# Nucleo.net
KiCad netlist of a schematic drawn in Altium Designer
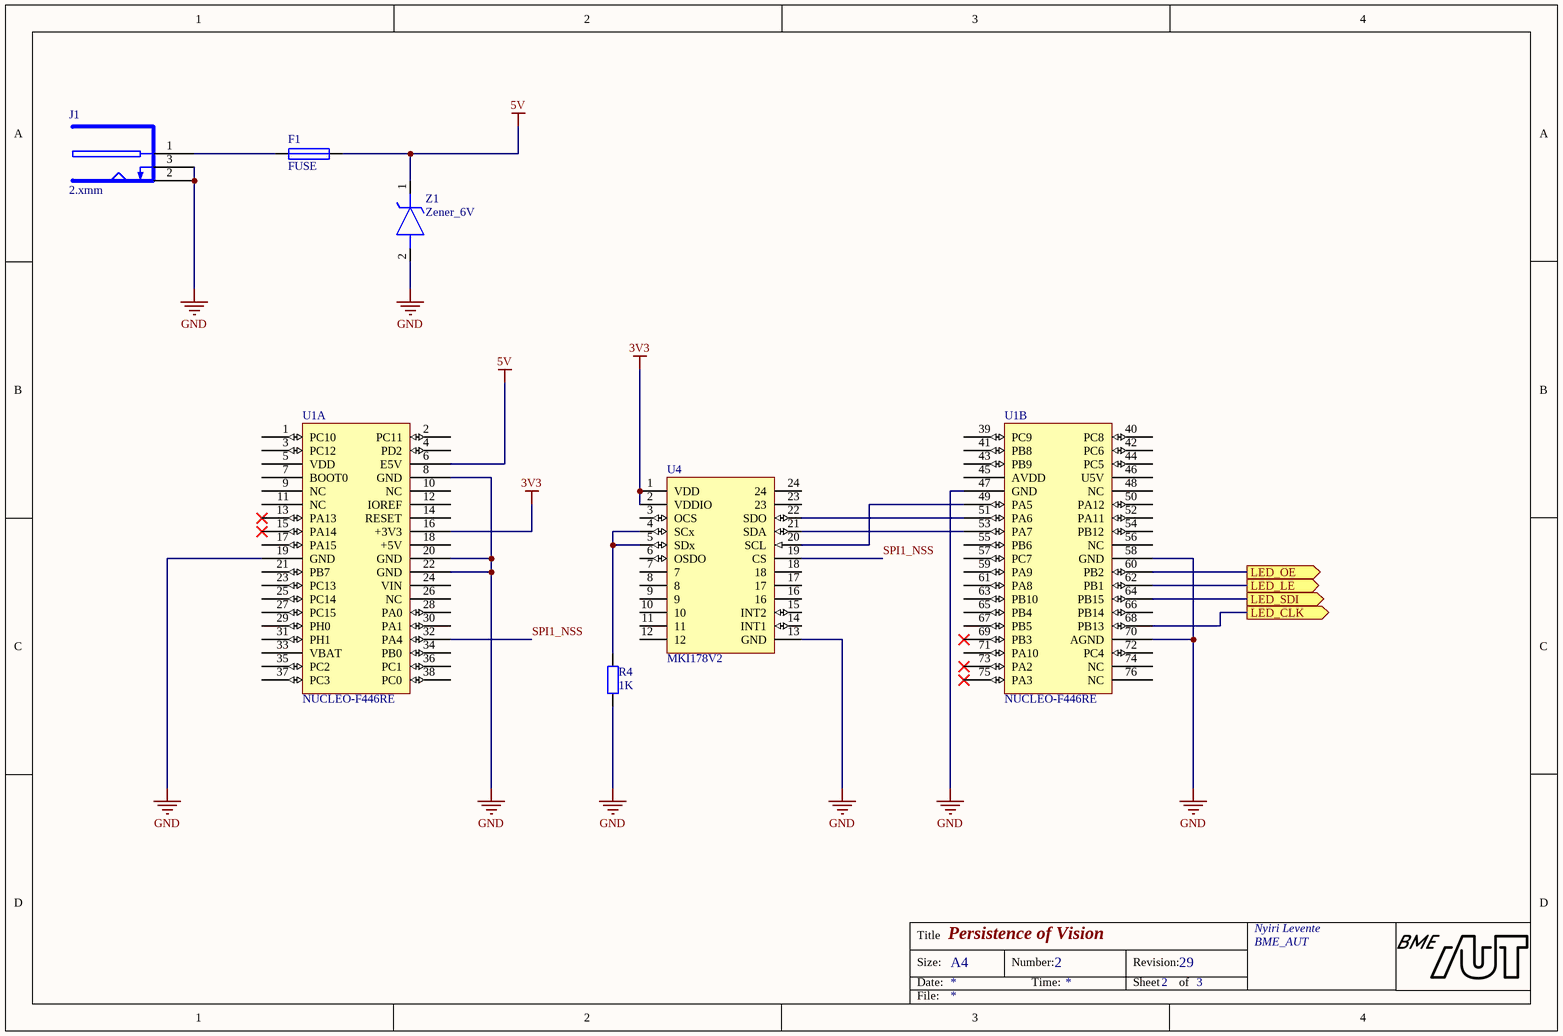
[diagram p0: Nucleo.SchDoc]

(export (version "E")
  (design (tool "Eeschema 10.0.6"))
  (components
    (comp (ref "F1")
      (value "FUSE")
      (footprint "1812L125/16DR2.0")
      (description "PTC Resettable Fuse, 16V, Surface Mount")
      (libsource (lib "hallglib") (part "1812L125/16DR"))
    )
    (comp (ref "J1")
      (value "2.xmm")
      (footprint "FP_DC_TAP_ANYA")
      (description "2.xmm DC HEBA25 TÁPFESZÜLTSÉG ALJZAT ZÁRT, NYÁKBA 90°")
      (libsource (lib "hallglib") (part "DC_TAP_ANYA"))
    )
    (comp (ref "R4")
      (value "1K")
      (footprint "FP_0805_RES")
      (description "Resistor")
      (libsource (lib "hallglib") (part "RES"))
    )
    (comp (ref "U1")
      (value "NUCLEO-F446RE")
      (footprint "FP_NUCLEO-64_2x20")
      (libsource (lib "hallglib") (part "NUCLEO-F446RE"))
    )
    (comp (ref "U4")
      (value "MKI178V2")
      (footprint "FP_DIL24")
      (description "LSM6DS3 inertial module adapter")
      (libsource (lib "hallglib") (part "MKI160V1"))
    )
    (comp (ref "Z1")
      (value "Zener_6V")
      (footprint "SOD2512X115N")
      (description "Zener Diode")
      (libsource (lib "hallglib") (part "BZT52C6V2S"))
    )
  )
  (nets
    (net (code "1") (name "/LED_CLK") (class "Default")
      (node (ref "U1") (pin "68") (pinfunction "PB13_68") (pintype "bidirectional"))
    )
    (net (code "2") (name "/LED_LE") (class "Default")
      (node (ref "U1") (pin "62") (pinfunction "PB1_62") (pintype "bidirectional"))
    )
    (net (code "3") (name "/LED_OE") (class "Default")
      (node (ref "U1") (pin "60") (pinfunction "PB2_60") (pintype "bidirectional"))
    )
    (net (code "4") (name "/LED_SDI") (class "Default")
      (node (ref "U1") (pin "64") (pinfunction "PB15_64") (pintype "bidirectional"))
    )
    (net (code "5") (name "/SPI1_NSS") (class "Default")
      (node (ref "U1") (pin "32") (pinfunction "PA4_32") (pintype "bidirectional"))
      (node (ref "U4") (pin "19") (pinfunction "CS_19") (pintype "passive"))
    )
    (net (code "6") (name "3V3") (class "Default")
      (node (ref "U1") (pin "16") (pinfunction "+3V3_16") (pintype "power_in"))
      (node (ref "U4") (pin "1") (pinfunction "VDD_1") (pintype "power_in"))
      (node (ref "U4") (pin "2") (pinfunction "VDDIO_2") (pintype "power_in"))
    )
    (net (code "7") (name "5V") (class "Default")
      (node (ref "F1") (pin "2") (pinfunction "2_2") (pintype "passive"))
      (node (ref "U1") (pin "6") (pinfunction "E5V_6") (pintype "power_in"))
      (node (ref "Z1") (pin "1") (pinfunction "K_1") (pintype "passive"))
    )
    (net (code "8") (name "GND") (class "Default")
      (node (ref "J1") (pin "2") (pinfunction "SLEEVE_2") (pintype "power_in"))
      (node (ref "J1") (pin "3") (pinfunction "BREAK_3") (pintype "power_in"))
      (node (ref "R4") (pin "1") (pinfunction "1_1") (pintype "passive"))
      (node (ref "U1") (pin "19") (pinfunction "GND_19") (pintype "passive"))
      (node (ref "U1") (pin "20") (pinfunction "GND_20") (pintype "passive"))
      (node (ref "U1") (pin "22") (pinfunction "GND_22") (pintype "passive"))
      (node (ref "U1") (pin "47") (pinfunction "GND_47") (pintype "passive"))
      (node (ref "U1") (pin "58") (pinfunction "GND_58") (pintype "passive"))
      (node (ref "U1") (pin "70") (pinfunction "AGND_70") (pintype "passive"))
      (node (ref "U1") (pin "8") (pinfunction "GND_8") (pintype "passive"))
      (node (ref "U4") (pin "13") (pinfunction "GND_13") (pintype "power_in"))
      (node (ref "Z1") (pin "2") (pinfunction "A_2") (pintype "passive"))
    )
    (net (code "9") (name "Net-(J1-PIN)") (class "Default")
      (node (ref "F1") (pin "1") (pinfunction "1_1") (pintype "passive"))
      (node (ref "J1") (pin "1") (pinfunction "PIN_1") (pintype "power_in"))
    )
    (net (code "10") (name "Net-(U1B-PA5)") (class "Default")
      (node (ref "U1") (pin "49") (pinfunction "PA5_49") (pintype "bidirectional"))
      (node (ref "U4") (pin "20") (pinfunction "SCL_20") (pintype "input"))
    )
    (net (code "11") (name "Net-(U1B-PA6)") (class "Default")
      (node (ref "U1") (pin "51") (pinfunction "PA6_51") (pintype "bidirectional"))
      (node (ref "U4") (pin "22") (pinfunction "SDO_22") (pintype "bidirectional"))
    )
    (net (code "12") (name "Net-(U1B-PA7)") (class "Default")
      (node (ref "U1") (pin "53") (pinfunction "PA7_53") (pintype "bidirectional"))
      (node (ref "U4") (pin "21") (pinfunction "SDA_21") (pintype "bidirectional"))
    )
    (net (code "13") (name "Net-(U4-SCx)") (class "Default")
      (node (ref "R4") (pin "2") (pinfunction "2_2") (pintype "passive"))
      (node (ref "U4") (pin "4") (pinfunction "SCx_4") (pintype "bidirectional"))
      (node (ref "U4") (pin "5") (pinfunction "SDx_5") (pintype "bidirectional"))
    )
    (net (code "14") (name "unconnected-(U1A-+5V-Pad18)") (class "Default")
      (node (ref "U1") (pin "18") (pinfunction "+5V_18") (pintype "power_in"))
    )
    (net (code "15") (name "unconnected-(U1A-BOOT0-Pad7)") (class "Default")
      (node (ref "U1") (pin "7") (pinfunction "BOOT0_7") (pintype "passive"))
    )
    (net (code "16") (name "unconnected-(U1A-IOREF-Pad12)") (class "Default")
      (node (ref "U1") (pin "12") (pinfunction "IOREF_12") (pintype "passive"))
    )
    (net (code "17") (name "unconnected-(U1A-NC-Pad9)") (class "Default")
      (node (ref "U1") (pin "9") (pinfunction "NC_9") (pintype "passive"))
    )
    (net (code "18") (name "unconnected-(U1A-NC-Pad10)") (class "Default")
      (node (ref "U1") (pin "10") (pinfunction "NC_10") (pintype "passive"))
    )
    (net (code "19") (name "unconnected-(U1A-NC-Pad11)") (class "Default")
      (node (ref "U1") (pin "11") (pinfunction "NC_11") (pintype "passive"))
    )
    (net (code "20") (name "unconnected-(U1A-NC-Pad26)") (class "Default")
      (node (ref "U1") (pin "26") (pinfunction "NC_26") (pintype "passive"))
    )
    (net (code "21") (name "unconnected-(U1A-PA0-Pad28)") (class "Default")
      (node (ref "U1") (pin "28") (pinfunction "PA0_28") (pintype "bidirectional"))
    )
    (net (code "22") (name "unconnected-(U1A-PA1-Pad30)") (class "Default")
      (node (ref "U1") (pin "30") (pinfunction "PA1_30") (pintype "bidirectional"))
    )
    (net (code "23") (name "unconnected-(U1A-PA13-Pad13)") (class "Default")
      (node (ref "U1") (pin "13") (pinfunction "PA13_13") (pintype "bidirectional+no_connect"))
    )
    (net (code "24") (name "unconnected-(U1A-PA14-Pad15)") (class "Default")
      (node (ref "U1") (pin "15") (pinfunction "PA14_15") (pintype "bidirectional+no_connect"))
    )
    (net (code "25") (name "unconnected-(U1A-PA15-Pad17)") (class "Default")
      (node (ref "U1") (pin "17") (pinfunction "PA15_17") (pintype "bidirectional"))
    )
    (net (code "26") (name "unconnected-(U1A-PB0-Pad34)") (class "Default")
      (node (ref "U1") (pin "34") (pinfunction "PB0_34") (pintype "bidirectional"))
    )
    (net (code "27") (name "unconnected-(U1A-PB7-Pad21)") (class "Default")
      (node (ref "U1") (pin "21") (pinfunction "PB7_21") (pintype "bidirectional"))
    )
    (net (code "28") (name "unconnected-(U1A-PC0-Pad38)") (class "Default")
      (node (ref "U1") (pin "38") (pinfunction "PC0_38") (pintype "bidirectional"))
    )
    (net (code "29") (name "unconnected-(U1A-PC1-Pad36)") (class "Default")
      (node (ref "U1") (pin "36") (pinfunction "PC1_36") (pintype "bidirectional"))
    )
    (net (code "30") (name "unconnected-(U1A-PC2-Pad35)") (class "Default")
      (node (ref "U1") (pin "35") (pinfunction "PC2_35") (pintype "bidirectional"))
    )
    (net (code "31") (name "unconnected-(U1A-PC3-Pad37)") (class "Default")
      (node (ref "U1") (pin "37") (pinfunction "PC3_37") (pintype "bidirectional"))
    )
    (net (code "32") (name "unconnected-(U1A-PC10-Pad1)") (class "Default")
      (node (ref "U1") (pin "1") (pinfunction "PC10_1") (pintype "bidirectional"))
    )
    (net (code "33") (name "unconnected-(U1A-PC11-Pad2)") (class "Default")
      (node (ref "U1") (pin "2") (pinfunction "PC11_2") (pintype "bidirectional"))
    )
    (net (code "34") (name "unconnected-(U1A-PC12-Pad3)") (class "Default")
      (node (ref "U1") (pin "3") (pinfunction "PC12_3") (pintype "bidirectional"))
    )
    (net (code "35") (name "unconnected-(U1A-PC13-Pad23)") (class "Default")
      (node (ref "U1") (pin "23") (pinfunction "PC13_23") (pintype "bidirectional"))
    )
    (net (code "36") (name "unconnected-(U1A-PC14-Pad25)") (class "Default")
      (node (ref "U1") (pin "25") (pinfunction "PC14_25") (pintype "bidirectional"))
    )
    (net (code "37") (name "unconnected-(U1A-PC15-Pad27)") (class "Default")
      (node (ref "U1") (pin "27") (pinfunction "PC15_27") (pintype "bidirectional"))
    )
    (net (code "38") (name "unconnected-(U1A-PD2-Pad4)") (class "Default")
      (node (ref "U1") (pin "4") (pinfunction "PD2_4") (pintype "bidirectional"))
    )
    (net (code "39") (name "unconnected-(U1A-PH0-Pad29)") (class "Default")
      (node (ref "U1") (pin "29") (pinfunction "PH0_29") (pintype "bidirectional"))
    )
    (net (code "40") (name "unconnected-(U1A-PH1-Pad31)") (class "Default")
      (node (ref "U1") (pin "31") (pinfunction "PH1_31") (pintype "bidirectional"))
    )
    (net (code "41") (name "unconnected-(U1A-RESET-Pad14)") (class "Default")
      (node (ref "U1") (pin "14") (pinfunction "RESET_14") (pintype "passive"))
    )
    (net (code "42") (name "unconnected-(U1A-VBAT-Pad33)") (class "Default")
      (node (ref "U1") (pin "33") (pinfunction "VBAT_33") (pintype "power_in"))
    )
    (net (code "43") (name "unconnected-(U1A-VDD-Pad5)") (class "Default")
      (node (ref "U1") (pin "5") (pinfunction "VDD_5") (pintype "power_in"))
    )
    (net (code "44") (name "unconnected-(U1A-VIN-Pad24)") (class "Default")
      (node (ref "U1") (pin "24") (pinfunction "VIN_24") (pintype "power_in"))
    )
    (net (code "45") (name "unconnected-(U1B-AVDD-Pad45)") (class "Default")
      (node (ref "U1") (pin "45") (pinfunction "AVDD_45") (pintype "power_in"))
    )
    (net (code "46") (name "unconnected-(U1B-NC-Pad48)") (class "Default")
      (node (ref "U1") (pin "48") (pinfunction "NC_48") (pintype "passive"))
    )
    (net (code "47") (name "unconnected-(U1B-NC-Pad56)") (class "Default")
      (node (ref "U1") (pin "56") (pinfunction "NC_56") (pintype "passive"))
    )
    (net (code "48") (name "unconnected-(U1B-NC-Pad74)") (class "Default")
      (node (ref "U1") (pin "74") (pinfunction "NC_74") (pintype "passive"))
    )
    (net (code "49") (name "unconnected-(U1B-NC-Pad76)") (class "Default")
      (node (ref "U1") (pin "76") (pinfunction "NC_76") (pintype "passive"))
    )
    (net (code "50") (name "unconnected-(U1B-PA2-Pad73)") (class "Default")
      (node (ref "U1") (pin "73") (pinfunction "PA2_73") (pintype "bidirectional+no_connect"))
    )
    (net (code "51") (name "unconnected-(U1B-PA3-Pad75)") (class "Default")
      (node (ref "U1") (pin "75") (pinfunction "PA3_75") (pintype "bidirectional+no_connect"))
    )
    (net (code "52") (name "unconnected-(U1B-PA8-Pad61)") (class "Default")
      (node (ref "U1") (pin "61") (pinfunction "PA8_61") (pintype "bidirectional"))
    )
    (net (code "53") (name "unconnected-(U1B-PA9-Pad59)") (class "Default")
      (node (ref "U1") (pin "59") (pinfunction "PA9_59") (pintype "bidirectional"))
    )
    (net (code "54") (name "unconnected-(U1B-PA10-Pad71)") (class "Default")
      (node (ref "U1") (pin "71") (pinfunction "PA10_71") (pintype "bidirectional"))
    )
    (net (code "55") (name "unconnected-(U1B-PA11-Pad52)") (class "Default")
      (node (ref "U1") (pin "52") (pinfunction "PA11_52") (pintype "bidirectional"))
    )
    (net (code "56") (name "unconnected-(U1B-PA12-Pad50)") (class "Default")
      (node (ref "U1") (pin "50") (pinfunction "PA12_50") (pintype "bidirectional"))
    )
    (net (code "57") (name "unconnected-(U1B-PB3-Pad69)") (class "Default")
      (node (ref "U1") (pin "69") (pinfunction "PB3_69") (pintype "bidirectional+no_connect"))
    )
    (net (code "58") (name "unconnected-(U1B-PB4-Pad65)") (class "Default")
      (node (ref "U1") (pin "65") (pinfunction "PB4_65") (pintype "bidirectional"))
    )
    (net (code "59") (name "unconnected-(U1B-PB5-Pad67)") (class "Default")
      (node (ref "U1") (pin "67") (pinfunction "PB5_67") (pintype "bidirectional"))
    )
    (net (code "60") (name "unconnected-(U1B-PB6-Pad55)") (class "Default")
      (node (ref "U1") (pin "55") (pinfunction "PB6_55") (pintype "bidirectional"))
    )
    (net (code "61") (name "unconnected-(U1B-PB8-Pad41)") (class "Default")
      (node (ref "U1") (pin "41") (pinfunction "PB8_41") (pintype "bidirectional"))
    )
    (net (code "62") (name "unconnected-(U1B-PB9-Pad43)") (class "Default")
      (node (ref "U1") (pin "43") (pinfunction "PB9_43") (pintype "bidirectional"))
    )
    (net (code "63") (name "unconnected-(U1B-PB10-Pad63)") (class "Default")
      (node (ref "U1") (pin "63") (pinfunction "PB10_63") (pintype "bidirectional"))
    )
    (net (code "64") (name "unconnected-(U1B-PB12-Pad54)") (class "Default")
      (node (ref "U1") (pin "54") (pinfunction "PB12_54") (pintype "bidirectional"))
    )
    (net (code "65") (name "unconnected-(U1B-PB14-Pad66)") (class "Default")
      (node (ref "U1") (pin "66") (pinfunction "PB14_66") (pintype "bidirectional"))
    )
    (net (code "66") (name "unconnected-(U1B-PC4-Pad72)") (class "Default")
      (node (ref "U1") (pin "72") (pinfunction "PC4_72") (pintype "bidirectional"))
    )
    (net (code "67") (name "unconnected-(U1B-PC5-Pad44)") (class "Default")
      (node (ref "U1") (pin "44") (pinfunction "PC5_44") (pintype "bidirectional"))
    )
    (net (code "68") (name "unconnected-(U1B-PC6-Pad42)") (class "Default")
      (node (ref "U1") (pin "42") (pinfunction "PC6_42") (pintype "bidirectional"))
    )
    (net (code "69") (name "unconnected-(U1B-PC7-Pad57)") (class "Default")
      (node (ref "U1") (pin "57") (pinfunction "PC7_57") (pintype "bidirectional"))
    )
    (net (code "70") (name "unconnected-(U1B-PC8-Pad40)") (class "Default")
      (node (ref "U1") (pin "40") (pinfunction "PC8_40") (pintype "bidirectional"))
    )
    (net (code "71") (name "unconnected-(U1B-PC9-Pad39)") (class "Default")
      (node (ref "U1") (pin "39") (pinfunction "PC9_39") (pintype "bidirectional"))
    )
    (net (code "72") (name "unconnected-(U1B-U5V-Pad46)") (class "Default")
      (node (ref "U1") (pin "46") (pinfunction "U5V_46") (pintype "power_in"))
    )
    (net (code "73") (name "unconnected-(U4-INT1-Pad14)") (class "Default")
      (node (ref "U4") (pin "14") (pinfunction "INT1_14") (pintype "bidirectional"))
    )
    (net (code "74") (name "unconnected-(U4-INT2-Pad15)") (class "Default")
      (node (ref "U4") (pin "15") (pinfunction "INT2_15") (pintype "bidirectional"))
    )
    (net (code "75") (name "unconnected-(U4-OCS-Pad3)") (class "Default")
      (node (ref "U4") (pin "3") (pinfunction "OCS_3") (pintype "bidirectional"))
    )
    (net (code "76") (name "unconnected-(U4-OSDO-Pad6)") (class "Default")
      (node (ref "U4") (pin "6") (pinfunction "OSDO_6") (pintype "bidirectional"))
    )
    (net (code "77") (name "unconnected-(U4-Pad7)") (class "Default")
      (node (ref "U4") (pin "7") (pinfunction "7_7") (pintype "passive"))
    )
    (net (code "78") (name "unconnected-(U4-Pad8)") (class "Default")
      (node (ref "U4") (pin "8") (pinfunction "8_8") (pintype "passive"))
    )
    (net (code "79") (name "unconnected-(U4-Pad9)") (class "Default")
      (node (ref "U4") (pin "9") (pinfunction "9_9") (pintype "passive"))
    )
    (net (code "80") (name "unconnected-(U4-Pad10)") (class "Default")
      (node (ref "U4") (pin "10") (pinfunction "10_10") (pintype "passive"))
    )
    (net (code "81") (name "unconnected-(U4-Pad11)") (class "Default")
      (node (ref "U4") (pin "11") (pinfunction "11_11") (pintype "passive"))
    )
    (net (code "82") (name "unconnected-(U4-Pad12)") (class "Default")
      (node (ref "U4") (pin "12") (pinfunction "12_12") (pintype "passive"))
    )
    (net (code "83") (name "unconnected-(U4-Pad16)") (class "Default")
      (node (ref "U4") (pin "16") (pinfunction "16_16") (pintype "passive"))
    )
    (net (code "84") (name "unconnected-(U4-Pad17)") (class "Default")
      (node (ref "U4") (pin "17") (pinfunction "17_17") (pintype "passive"))
    )
    (net (code "85") (name "unconnected-(U4-Pad18)") (class "Default")
      (node (ref "U4") (pin "18") (pinfunction "18_18") (pintype "passive"))
    )
    (net (code "86") (name "unconnected-(U4-Pad23)") (class "Default")
      (node (ref "U4") (pin "23") (pinfunction "23_23") (pintype "passive"))
    )
    (net (code "87") (name "unconnected-(U4-Pad24)") (class "Default")
      (node (ref "U4") (pin "24") (pinfunction "24_24") (pintype "passive"))
    )
  )
)
